# sensor_board.net
KiCad netlist of a schematic drawn in EAGLE
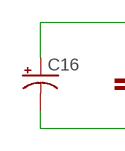
[diagram p0: schematic, sheet 1, part 1 of 2]
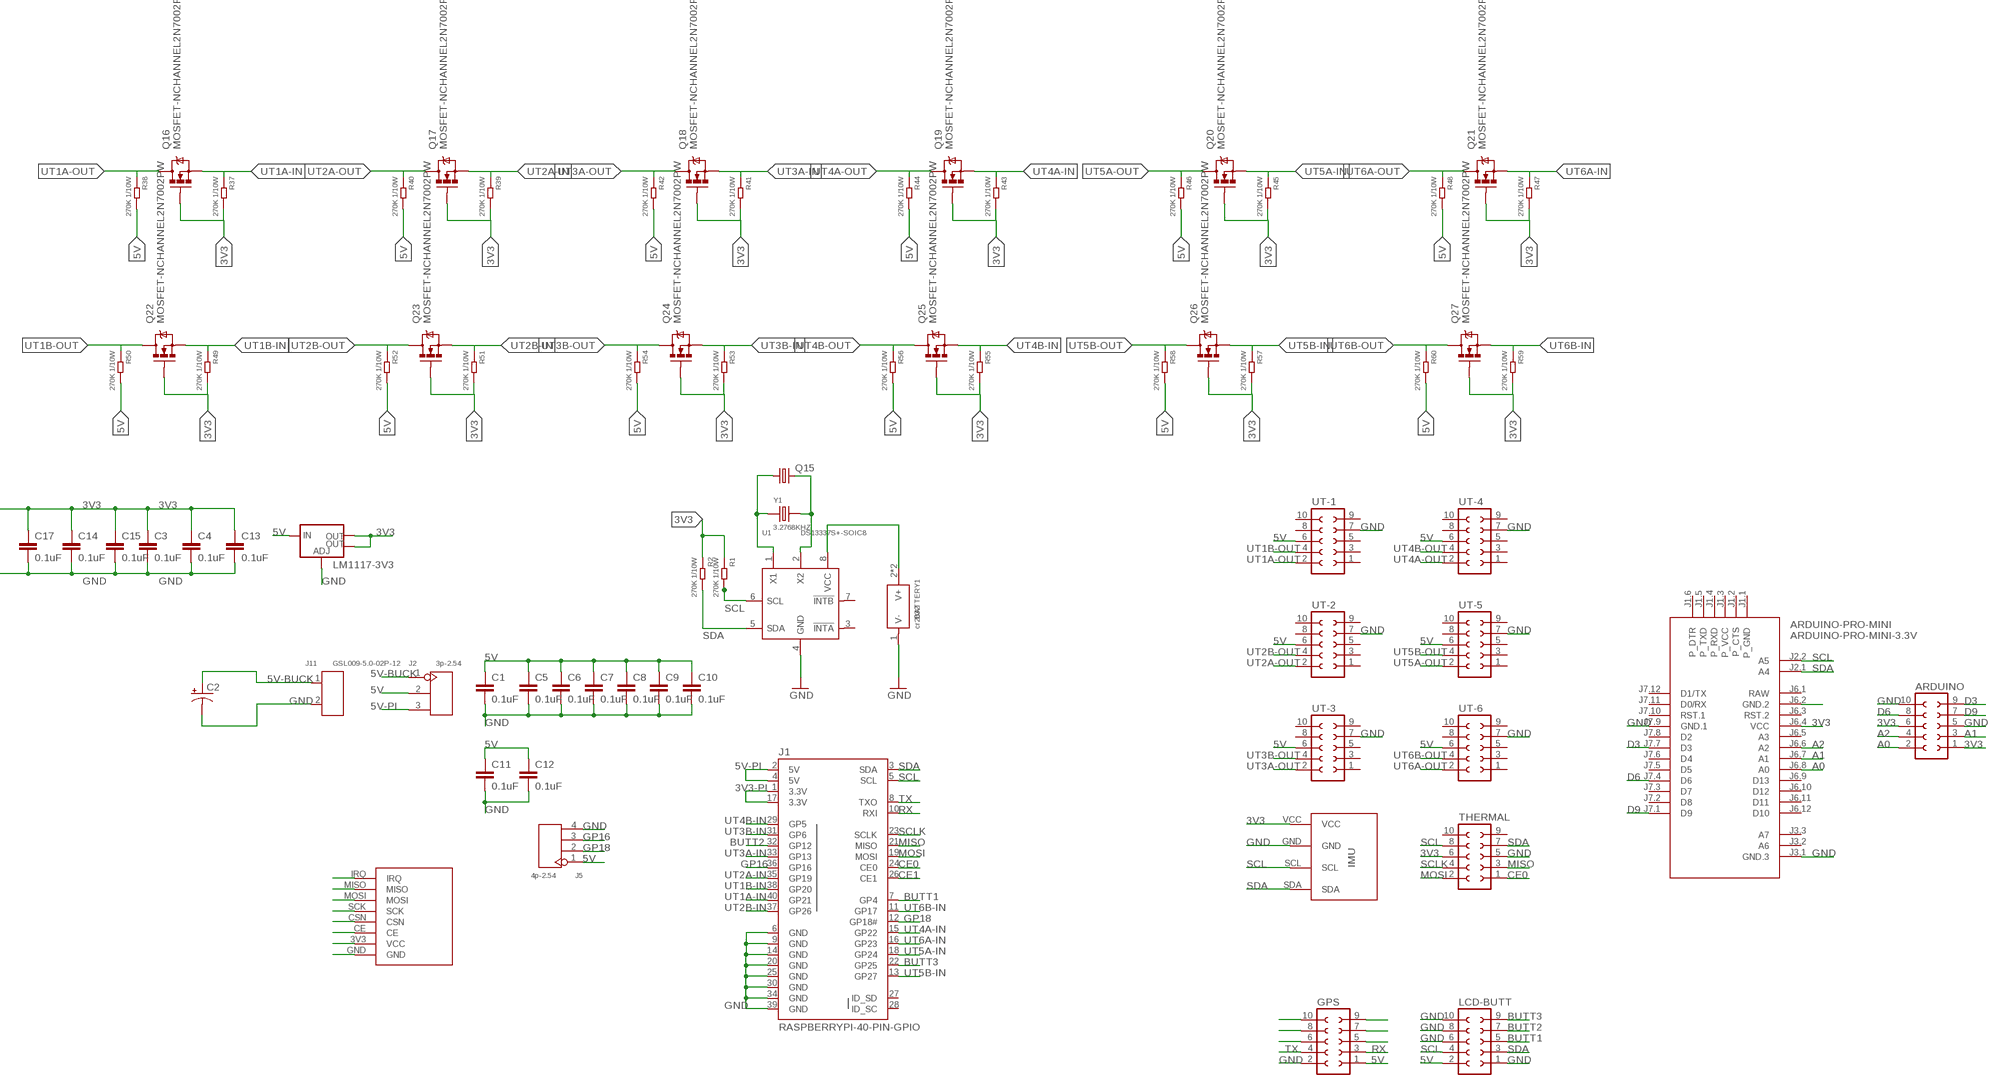
[diagram p1: schematic, sheet 1, part 2 of 2]

(export (version "E")
  (design (tool "Eeschema 10.0.6"))
  (components
    (comp (ref "ARDUINO")
      (value "SOCKET-10V")
      (footprint "eagle-import:S10V")
      (libsource (lib "eagle-import") (part "SOCKET-10V"))
    )
    (comp (ref "ARDUINO-PRO-MINI")
      (value "ARDUINO-PRO-MINI-3.3V")
      (footprint "eagle-import:ARDUINO-PRO-MINI")
      (libsource (lib "eagle-import") (part "ARDUINO-PRO-MINI-3.3V"))
    )
    (comp (ref "BATTERY1")
      (value "cr2032")
      (footprint "eagle-import:BAT2P-20.32-CR2032")
      (libsource (lib "eagle-import") (part "DIP-BATTERY-CELL-HOLDER(2032)"))
    )
    (comp (ref "C1")
      (value "0.1uF")
      (footprint "eagle-import:0603-CAP")
      (libsource (lib "eagle-import") (part "0.1UF-100V-10%(0603)"))
    )
    (comp (ref "C2")
      (value "100UF-25V-20%(PTH)")
      (footprint "eagle-import:CPOL-RADIAL-100UF-25V")
      (libsource (lib "eagle-import") (part "100UF-25V-20%(PTH)"))
    )
    (comp (ref "C3")
      (value "0.1uF")
      (footprint "eagle-import:0603-CAP")
      (libsource (lib "eagle-import") (part "0.1UF-100V-10%(0603)"))
    )
    (comp (ref "C4")
      (value "0.1uF")
      (footprint "eagle-import:0603-CAP")
      (libsource (lib "eagle-import") (part "0.1UF-100V-10%(0603)"))
    )
    (comp (ref "C5")
      (value "0.1uF")
      (footprint "eagle-import:0603-CAP")
      (libsource (lib "eagle-import") (part "0.1UF-100V-10%(0603)"))
    )
    (comp (ref "C6")
      (value "0.1uF")
      (footprint "eagle-import:0603-CAP")
      (libsource (lib "eagle-import") (part "0.1UF-100V-10%(0603)"))
    )
    (comp (ref "C7")
      (value "0.1uF")
      (footprint "eagle-import:0603-CAP")
      (libsource (lib "eagle-import") (part "0.1UF-100V-10%(0603)"))
    )
    (comp (ref "C8")
      (value "0.1uF")
      (footprint "eagle-import:0603-CAP")
      (libsource (lib "eagle-import") (part "0.1UF-100V-10%(0603)"))
    )
    (comp (ref "C9")
      (value "0.1uF")
      (footprint "eagle-import:0603-CAP")
      (libsource (lib "eagle-import") (part "0.1UF-100V-10%(0603)"))
    )
    (comp (ref "C10")
      (value "0.1uF")
      (footprint "eagle-import:0603-CAP")
      (libsource (lib "eagle-import") (part "0.1UF-100V-10%(0603)"))
    )
    (comp (ref "C11")
      (value "0.1uF")
      (footprint "eagle-import:0603-CAP")
      (libsource (lib "eagle-import") (part "0.1UF-100V-10%(0603)"))
    )
    (comp (ref "C12")
      (value "0.1uF")
      (footprint "eagle-import:0603-CAP")
      (libsource (lib "eagle-import") (part "0.1UF-100V-10%(0603)"))
    )
    (comp (ref "C13")
      (value "0.1uF")
      (footprint "eagle-import:0603-CAP")
      (libsource (lib "eagle-import") (part "0.1UF-100V-10%(0603)"))
    )
    (comp (ref "C14")
      (value "0.1uF")
      (footprint "eagle-import:0603-CAP")
      (libsource (lib "eagle-import") (part "0.1UF-100V-10%(0603)"))
    )
    (comp (ref "C15")
      (value "0.1uF")
      (footprint "eagle-import:0603-CAP")
      (libsource (lib "eagle-import") (part "0.1UF-100V-10%(0603)"))
    )
    (comp (ref "C16")
      (value "100UF-25V-20%(PTH)")
      (footprint "eagle-import:CPOL-RADIAL-100UF-25V")
      (libsource (lib "eagle-import") (part "100UF-25V-20%(PTH)"))
    )
    (comp (ref "C17")
      (value "0.1uF")
      (footprint "eagle-import:0603-CAP")
      (libsource (lib "eagle-import") (part "0.1UF-100V-10%(0603)"))
    )
    (comp (ref "GPS")
      (value "SOCKET-10V")
      (footprint "eagle-import:S10V")
      (libsource (lib "eagle-import") (part "SOCKET-10V"))
    )
    (comp (ref "J1")
      (value "RASPBERRYPI-40-PIN-GPIO")
      (footprint "eagle-import:2X20-SHROUDED")
      (libsource (lib "eagle-import") (part "RASPBERRYPI-40-PIN-GPIO"))
    )
    (comp (ref "J2")
      (value "3p-2.54")
      (footprint "eagle-import:H3-2.54")
      (fields (field (name "MPN") "F185-1103A0BSYA1"))
      (libsource (lib "eagle-import") (part "DIP-BLACK-FEMALE-HEADER-VERT(3P-2.54)"))
    )
    (comp (ref "J5")
      (value "4p-2.54")
      (footprint "eagle-import:H4-2.54")
      (fields (field (name "MPN") "F185-1104A1BSYA1"))
      (libsource (lib "eagle-import") (part "DIP-BLACK-FEMALE-HEADER-VERT(4P-2.54)"))
    )
    (comp (ref "J11")
      (value "GSL009-5.0-02P-12")
      (footprint "eagle-import:H2-5.0-10.5X8.0MM")
      (libsource (lib "eagle-import") (part "SCREW-TERMINAL-BLUE(2P-5.0)"))
    )
    (comp (ref "LCD-BUTT")
      (value "SOCKET-10V")
      (footprint "eagle-import:S10V")
      (libsource (lib "eagle-import") (part "SOCKET-10V"))
    )
    (comp (ref "LM1117-3V3")
      (value "V_REG_LM1117SOT223")
      (footprint "eagle-import:SOT223")
      (libsource (lib "eagle-import") (part "V_REG_LM1117SOT223"))
    )
    (comp (ref "Q15")
      (value "CRYSTALTC26H")
      (footprint "eagle-import:TC26H")
      (libsource (lib "eagle-import") (part "CRYSTALTC26H"))
    )
    (comp (ref "Q16")
      (value "MOSFET-NCHANNEL2N7002PW")
      (footprint "eagle-import:SOT323")
      (libsource (lib "eagle-import") (part "MOSFET-NCHANNEL2N7002PW"))
    )
    (comp (ref "Q17")
      (value "MOSFET-NCHANNEL2N7002PW")
      (footprint "eagle-import:SOT323")
      (libsource (lib "eagle-import") (part "MOSFET-NCHANNEL2N7002PW"))
    )
    (comp (ref "Q18")
      (value "MOSFET-NCHANNEL2N7002PW")
      (footprint "eagle-import:SOT323")
      (libsource (lib "eagle-import") (part "MOSFET-NCHANNEL2N7002PW"))
    )
    (comp (ref "Q19")
      (value "MOSFET-NCHANNEL2N7002PW")
      (footprint "eagle-import:SOT323")
      (libsource (lib "eagle-import") (part "MOSFET-NCHANNEL2N7002PW"))
    )
    (comp (ref "Q20")
      (value "MOSFET-NCHANNEL2N7002PW")
      (footprint "eagle-import:SOT323")
      (libsource (lib "eagle-import") (part "MOSFET-NCHANNEL2N7002PW"))
    )
    (comp (ref "Q21")
      (value "MOSFET-NCHANNEL2N7002PW")
      (footprint "eagle-import:SOT323")
      (libsource (lib "eagle-import") (part "MOSFET-NCHANNEL2N7002PW"))
    )
    (comp (ref "Q22")
      (value "MOSFET-NCHANNEL2N7002PW")
      (footprint "eagle-import:SOT323")
      (libsource (lib "eagle-import") (part "MOSFET-NCHANNEL2N7002PW"))
    )
    (comp (ref "Q23")
      (value "MOSFET-NCHANNEL2N7002PW")
      (footprint "eagle-import:SOT323")
      (libsource (lib "eagle-import") (part "MOSFET-NCHANNEL2N7002PW"))
    )
    (comp (ref "Q24")
      (value "MOSFET-NCHANNEL2N7002PW")
      (footprint "eagle-import:SOT323")
      (libsource (lib "eagle-import") (part "MOSFET-NCHANNEL2N7002PW"))
    )
    (comp (ref "Q25")
      (value "MOSFET-NCHANNEL2N7002PW")
      (footprint "eagle-import:SOT323")
      (libsource (lib "eagle-import") (part "MOSFET-NCHANNEL2N7002PW"))
    )
    (comp (ref "Q26")
      (value "MOSFET-NCHANNEL2N7002PW")
      (footprint "eagle-import:SOT323")
      (libsource (lib "eagle-import") (part "MOSFET-NCHANNEL2N7002PW"))
    )
    (comp (ref "Q27")
      (value "MOSFET-NCHANNEL2N7002PW")
      (footprint "eagle-import:SOT323")
      (libsource (lib "eagle-import") (part "MOSFET-NCHANNEL2N7002PW"))
    )
    (comp (ref "R1")
      (value "270K 1/10W")
      (footprint "eagle-import:R0603")
      (fields (field (name "MPN") "RC0603FR-07270KL"))
      (libsource (lib "eagle-import") (part "RC0603FR-0720RL(0603)"))
    )
    (comp (ref "R2")
      (value "270K 1/10W")
      (footprint "eagle-import:R0603")
      (fields (field (name "MPN") "RC0603FR-07270KL"))
      (libsource (lib "eagle-import") (part "RC0603FR-0720RL(0603)"))
    )
    (comp (ref "R37")
      (value "270K 1/10W")
      (footprint "eagle-import:R0603")
      (fields (field (name "MPN") "RC0603FR-07270KL"))
      (libsource (lib "eagle-import") (part "RC0603FR-0720RL(0603)"))
    )
    (comp (ref "R38")
      (value "270K 1/10W")
      (footprint "eagle-import:R0603")
      (fields (field (name "MPN") "RC0603FR-07270KL"))
      (libsource (lib "eagle-import") (part "RC0603FR-0720RL(0603)"))
    )
    (comp (ref "R39")
      (value "270K 1/10W")
      (footprint "eagle-import:R0603")
      (fields (field (name "MPN") "RC0603FR-07270KL"))
      (libsource (lib "eagle-import") (part "RC0603FR-0720RL(0603)"))
    )
    (comp (ref "R40")
      (value "270K 1/10W")
      (footprint "eagle-import:R0603")
      (fields (field (name "MPN") "RC0603FR-07270KL"))
      (libsource (lib "eagle-import") (part "RC0603FR-0720RL(0603)"))
    )
    (comp (ref "R41")
      (value "270K 1/10W")
      (footprint "eagle-import:R0603")
      (fields (field (name "MPN") "RC0603FR-07270KL"))
      (libsource (lib "eagle-import") (part "RC0603FR-0720RL(0603)"))
    )
    (comp (ref "R42")
      (value "270K 1/10W")
      (footprint "eagle-import:R0603")
      (fields (field (name "MPN") "RC0603FR-07270KL"))
      (libsource (lib "eagle-import") (part "RC0603FR-0720RL(0603)"))
    )
    (comp (ref "R43")
      (value "270K 1/10W")
      (footprint "eagle-import:R0603")
      (fields (field (name "MPN") "RC0603FR-07270KL"))
      (libsource (lib "eagle-import") (part "RC0603FR-0720RL(0603)"))
    )
    (comp (ref "R44")
      (value "270K 1/10W")
      (footprint "eagle-import:R0603")
      (fields (field (name "MPN") "RC0603FR-07270KL"))
      (libsource (lib "eagle-import") (part "RC0603FR-0720RL(0603)"))
    )
    (comp (ref "R45")
      (value "270K 1/10W")
      (footprint "eagle-import:R0603")
      (fields (field (name "MPN") "RC0603FR-07270KL"))
      (libsource (lib "eagle-import") (part "RC0603FR-0720RL(0603)"))
    )
    (comp (ref "R46")
      (value "270K 1/10W")
      (footprint "eagle-import:R0603")
      (fields (field (name "MPN") "RC0603FR-07270KL"))
      (libsource (lib "eagle-import") (part "RC0603FR-0720RL(0603)"))
    )
    (comp (ref "R47")
      (value "270K 1/10W")
      (footprint "eagle-import:R0603")
      (fields (field (name "MPN") "RC0603FR-07270KL"))
      (libsource (lib "eagle-import") (part "RC0603FR-0720RL(0603)"))
    )
    (comp (ref "R48")
      (value "270K 1/10W")
      (footprint "eagle-import:R0603")
      (fields (field (name "MPN") "RC0603FR-07270KL"))
      (libsource (lib "eagle-import") (part "RC0603FR-0720RL(0603)"))
    )
    (comp (ref "R49")
      (value "270K 1/10W")
      (footprint "eagle-import:R0603")
      (fields (field (name "MPN") "RC0603FR-07270KL"))
      (libsource (lib "eagle-import") (part "RC0603FR-0720RL(0603)"))
    )
    (comp (ref "R50")
      (value "270K 1/10W")
      (footprint "eagle-import:R0603")
      (fields (field (name "MPN") "RC0603FR-07270KL"))
      (libsource (lib "eagle-import") (part "RC0603FR-0720RL(0603)"))
    )
    (comp (ref "R51")
      (value "270K 1/10W")
      (footprint "eagle-import:R0603")
      (fields (field (name "MPN") "RC0603FR-07270KL"))
      (libsource (lib "eagle-import") (part "RC0603FR-0720RL(0603)"))
    )
    (comp (ref "R52")
      (value "270K 1/10W")
      (footprint "eagle-import:R0603")
      (fields (field (name "MPN") "RC0603FR-07270KL"))
      (libsource (lib "eagle-import") (part "RC0603FR-0720RL(0603)"))
    )
    (comp (ref "R53")
      (value "270K 1/10W")
      (footprint "eagle-import:R0603")
      (fields (field (name "MPN") "RC0603FR-07270KL"))
      (libsource (lib "eagle-import") (part "RC0603FR-0720RL(0603)"))
    )
    (comp (ref "R54")
      (value "270K 1/10W")
      (footprint "eagle-import:R0603")
      (fields (field (name "MPN") "RC0603FR-07270KL"))
      (libsource (lib "eagle-import") (part "RC0603FR-0720RL(0603)"))
    )
    (comp (ref "R55")
      (value "270K 1/10W")
      (footprint "eagle-import:R0603")
      (fields (field (name "MPN") "RC0603FR-07270KL"))
      (libsource (lib "eagle-import") (part "RC0603FR-0720RL(0603)"))
    )
    (comp (ref "R56")
      (value "270K 1/10W")
      (footprint "eagle-import:R0603")
      (fields (field (name "MPN") "RC0603FR-07270KL"))
      (libsource (lib "eagle-import") (part "RC0603FR-0720RL(0603)"))
    )
    (comp (ref "R57")
      (value "270K 1/10W")
      (footprint "eagle-import:R0603")
      (fields (field (name "MPN") "RC0603FR-07270KL"))
      (libsource (lib "eagle-import") (part "RC0603FR-0720RL(0603)"))
    )
    (comp (ref "R58")
      (value "270K 1/10W")
      (footprint "eagle-import:R0603")
      (fields (field (name "MPN") "RC0603FR-07270KL"))
      (libsource (lib "eagle-import") (part "RC0603FR-0720RL(0603)"))
    )
    (comp (ref "R59")
      (value "270K 1/10W")
      (footprint "eagle-import:R0603")
      (fields (field (name "MPN") "RC0603FR-07270KL"))
      (libsource (lib "eagle-import") (part "RC0603FR-0720RL(0603)"))
    )
    (comp (ref "R60")
      (value "270K 1/10W")
      (footprint "eagle-import:R0603")
      (fields (field (name "MPN") "RC0603FR-07270KL"))
      (libsource (lib "eagle-import") (part "RC0603FR-0720RL(0603)"))
    )
    (comp (ref "THERMAL")
      (value "SOCKET-10V")
      (footprint "eagle-import:S10V")
      (libsource (lib "eagle-import") (part "SOCKET-10V"))
    )
    (comp (ref "U$1")
      (value "IMU")
      (footprint "eagle-import:IMU")
      (libsource (lib "eagle-import") (part "IMU"))
    )
    (comp (ref "U$2")
      (value "NRF24L01+")
      (footprint "eagle-import:NRF24L01+")
      (libsource (lib "eagle-import") (part "NRF24L01+"))
    )
    (comp (ref "U1")
      (value "DS13337S+-SOIC8")
      (footprint "eagle-import:SOIC8-1.27-5X4MM")
      (fields (field (name "MPN") "DS1337S+"))
      (libsource (lib "eagle-import") (part "CLOCK-DS1337S+(SOIC8)"))
    )
    (comp (ref "UT-1")
      (value "SOCKET-10V")
      (footprint "eagle-import:S10V")
      (libsource (lib "eagle-import") (part "SOCKET-10V"))
    )
    (comp (ref "UT-2")
      (value "SOCKET-10V")
      (footprint "eagle-import:S10V")
      (libsource (lib "eagle-import") (part "SOCKET-10V"))
    )
    (comp (ref "UT-3")
      (value "SOCKET-10V")
      (footprint "eagle-import:S10V")
      (libsource (lib "eagle-import") (part "SOCKET-10V"))
    )
    (comp (ref "UT-4")
      (value "SOCKET-10V")
      (footprint "eagle-import:S10V")
      (libsource (lib "eagle-import") (part "SOCKET-10V"))
    )
    (comp (ref "UT-5")
      (value "SOCKET-10V")
      (footprint "eagle-import:S10V")
      (libsource (lib "eagle-import") (part "SOCKET-10V"))
    )
    (comp (ref "UT-6")
      (value "SOCKET-10V")
      (footprint "eagle-import:S10V")
      (libsource (lib "eagle-import") (part "SOCKET-10V"))
    )
    (comp (ref "Y1")
      (value "3.2768KHZ")
      (footprint "eagle-import:X2-SMD-L2.0X1.2X0.55MM")
      (fields (field (name "MPN") "FC-12M"))
      (libsource (lib "eagle-import") (part "SMD-CRYSTAL-32.768KHZ-12.5PF-20PPM-90K(2P-L2.0X1.2MM)"))
    )
  )
  (nets
    (net (code "1") (name "/3V3-PI") (class "Default")
      (node (ref "J1") (pin "1") (pinfunction "3.3V_1") (pintype "power_in"))
      (node (ref "J1") (pin "17") (pinfunction "3.3V_17") (pintype "power_in"))
    )
    (net (code "2") (name "/5V-BUCK") (class "Default")
      (node (ref "C2") (pin "1") (pinfunction "+_1") (pintype "passive"))
      (node (ref "J11") (pin "1") (pinfunction "1_1") (pintype "bidirectional"))
      (node (ref "J2") (pin "1") (pinfunction "P$1_1") (pintype "bidirectional"))
    )
    (net (code "3") (name "/5V-PI") (class "Default")
      (node (ref "J1") (pin "2") (pinfunction "5V_2") (pintype "power_in"))
      (node (ref "J1") (pin "4") (pinfunction "5V_4") (pintype "power_in"))
      (node (ref "J2") (pin "3") (pinfunction "P$3_3") (pintype "bidirectional"))
    )
    (net (code "4") (name "/A0") (class "Default")
      (node (ref "ARDUINO") (pin "2") (pinfunction "2_2") (pintype "passive"))
      (node (ref "ARDUINO-PRO-MINI") (pin "J6.8") (pinfunction "A0_J6.8") (pintype "bidirectional"))
    )
    (net (code "5") (name "/A1") (class "Default")
      (node (ref "ARDUINO") (pin "3") (pinfunction "3_3") (pintype "passive"))
      (node (ref "ARDUINO-PRO-MINI") (pin "J6.7") (pinfunction "A1_J6.7") (pintype "bidirectional"))
    )
    (net (code "6") (name "/A2") (class "Default")
      (node (ref "ARDUINO") (pin "4") (pinfunction "4_4") (pintype "passive"))
      (node (ref "ARDUINO-PRO-MINI") (pin "J6.6") (pinfunction "A2_J6.6") (pintype "bidirectional"))
    )
    (net (code "7") (name "/BUTT1") (class "Default")
      (node (ref "J1") (pin "7") (pinfunction "GP4_7") (pintype "bidirectional"))
      (node (ref "LCD-BUTT") (pin "5") (pinfunction "5_5") (pintype "passive"))
    )
    (net (code "8") (name "/BUTT2") (class "Default")
      (node (ref "J1") (pin "32") (pinfunction "GP12_32") (pintype "bidirectional"))
      (node (ref "LCD-BUTT") (pin "7") (pinfunction "7_7") (pintype "passive"))
    )
    (net (code "9") (name "/BUTT3") (class "Default")
      (node (ref "J1") (pin "22") (pinfunction "GP25_22") (pintype "bidirectional"))
      (node (ref "LCD-BUTT") (pin "9") (pinfunction "9_9") (pintype "passive"))
      (node (ref "U$2") (pin "CE") (pinfunction "CE_CE") (pintype "bidirectional"))
    )
    (net (code "10") (name "/CE0") (class "Default")
      (node (ref "J1") (pin "24") (pinfunction "CE0_24") (pintype "output"))
      (node (ref "THERMAL") (pin "1") (pinfunction "1_1") (pintype "passive"))
    )
    (net (code "11") (name "/CE1") (class "Default")
      (node (ref "J1") (pin "26") (pinfunction "CE1_26") (pintype "output"))
      (node (ref "U$2") (pin "CSN") (pinfunction "CSN_CSN") (pintype "bidirectional"))
    )
    (net (code "12") (name "/D3") (class "Default")
      (node (ref "ARDUINO") (pin "9") (pinfunction "9_9") (pintype "passive"))
      (node (ref "ARDUINO-PRO-MINI") (pin "J7.7") (pinfunction "D3_J7.7") (pintype "bidirectional"))
    )
    (net (code "13") (name "/D6") (class "Default")
      (node (ref "ARDUINO") (pin "8") (pinfunction "8_8") (pintype "passive"))
      (node (ref "ARDUINO-PRO-MINI") (pin "J7.4") (pinfunction "D6_J7.4") (pintype "bidirectional"))
    )
    (net (code "14") (name "/D9") (class "Default")
      (node (ref "ARDUINO") (pin "7") (pinfunction "7_7") (pintype "passive"))
      (node (ref "ARDUINO-PRO-MINI") (pin "J7.1") (pinfunction "D9_J7.1") (pintype "bidirectional"))
    )
    (net (code "15") (name "/GP16") (class "Default")
      (node (ref "J1") (pin "36") (pinfunction "GP16_36") (pintype "bidirectional"))
      (node (ref "J5") (pin "3") (pinfunction "P$3_3") (pintype "bidirectional"))
    )
    (net (code "16") (name "/GP18") (class "Default")
      (node (ref "J1") (pin "12") (pinfunction "GP18#_12") (pintype "bidirectional"))
      (node (ref "J5") (pin "2") (pinfunction "P$2_2") (pintype "bidirectional"))
    )
    (net (code "17") (name "/MISO") (class "Default")
      (node (ref "J1") (pin "21") (pinfunction "MISO_21") (pintype "input"))
      (node (ref "THERMAL") (pin "3") (pinfunction "3_3") (pintype "passive"))
      (node (ref "U$2") (pin "MISO") (pinfunction "MISO_MISO") (pintype "bidirectional"))
    )
    (net (code "18") (name "/MOSI") (class "Default")
      (node (ref "J1") (pin "19") (pinfunction "MOSI_19") (pintype "output"))
      (node (ref "THERMAL") (pin "2") (pinfunction "2_2") (pintype "passive"))
      (node (ref "U$2") (pin "MOSI") (pinfunction "MOSI_MOSI") (pintype "bidirectional"))
    )
    (net (code "19") (name "/RAW") (class "Default")
      (node (ref "ARDUINO-PRO-MINI") (pin "J6.1") (pinfunction "RAW_J6.1") (pintype "power_in"))
    )
    (net (code "20") (name "/RX") (class "Default")
      (node (ref "GPS") (pin "3") (pinfunction "3_3") (pintype "passive"))
      (node (ref "J1") (pin "10") (pinfunction "RXI_10") (pintype "input"))
    )
    (net (code "21") (name "/SCL") (class "Default")
      (node (ref "ARDUINO-PRO-MINI") (pin "J2.2") (pinfunction "A5_J2.2") (pintype "bidirectional"))
      (node (ref "J1") (pin "5") (pinfunction "SCL_5") (pintype "bidirectional"))
      (node (ref "LCD-BUTT") (pin "4") (pinfunction "4_4") (pintype "passive"))
      (node (ref "R1") (pin "2") (pinfunction "2_2") (pintype "passive"))
      (node (ref "THERMAL") (pin "8") (pinfunction "8_8") (pintype "passive"))
      (node (ref "U$1") (pin "SCL") (pinfunction "SCL_SCL") (pintype "bidirectional"))
      (node (ref "U1") (pin "6") (pinfunction "SCL_6") (pintype "bidirectional"))
    )
    (net (code "22") (name "/SCLK") (class "Default")
      (node (ref "J1") (pin "23") (pinfunction "SCLK_23") (pintype "output"))
      (node (ref "THERMAL") (pin "4") (pinfunction "4_4") (pintype "passive"))
      (node (ref "U$2") (pin "SCK") (pinfunction "SCK_SCK") (pintype "bidirectional"))
    )
    (net (code "23") (name "/SDA") (class "Default")
      (node (ref "ARDUINO-PRO-MINI") (pin "J2.1") (pinfunction "A4_J2.1") (pintype "bidirectional"))
      (node (ref "J1") (pin "3") (pinfunction "SDA_3") (pintype "bidirectional"))
      (node (ref "LCD-BUTT") (pin "3") (pinfunction "3_3") (pintype "passive"))
      (node (ref "R2") (pin "2") (pinfunction "2_2") (pintype "passive"))
      (node (ref "THERMAL") (pin "7") (pinfunction "7_7") (pintype "passive"))
      (node (ref "U$1") (pin "SDA") (pinfunction "SDA_SDA") (pintype "bidirectional"))
      (node (ref "U1") (pin "5") (pinfunction "SDA_5") (pintype "bidirectional"))
    )
    (net (code "24") (name "/TX") (class "Default")
      (node (ref "GPS") (pin "4") (pinfunction "4_4") (pintype "passive"))
      (node (ref "J1") (pin "8") (pinfunction "TXO_8") (pintype "output"))
    )
    (net (code "25") (name "3V3") (class "Default")
      (node (ref "ARDUINO") (pin "1") (pinfunction "1_1") (pintype "passive"))
      (node (ref "ARDUINO") (pin "6") (pinfunction "6_6") (pintype "passive"))
      (node (ref "ARDUINO-PRO-MINI") (pin "J6.4") (pinfunction "VCC_J6.4") (pintype "power_in"))
      (node (ref "C13") (pin "1") (pinfunction "1_1") (pintype "passive"))
      (node (ref "C14") (pin "1") (pinfunction "1_1") (pintype "passive"))
      (node (ref "C15") (pin "1") (pinfunction "1_1") (pintype "passive"))
      (node (ref "C16") (pin "1") (pinfunction "+_1") (pintype "passive"))
      (node (ref "C17") (pin "1") (pinfunction "1_1") (pintype "passive"))
      (node (ref "C3") (pin "1") (pinfunction "1_1") (pintype "passive"))
      (node (ref "C4") (pin "1") (pinfunction "1_1") (pintype "passive"))
      (node (ref "LM1117-3V3") (pin "2") (pinfunction "OUT_2") (pintype "output"))
      (node (ref "LM1117-3V3") (pin "4") (pinfunction "OUT_4") (pintype "output"))
      (node (ref "Q16") (pin "1") (pinfunction "G_1") (pintype "passive"))
      (node (ref "Q17") (pin "1") (pinfunction "G_1") (pintype "passive"))
      (node (ref "Q18") (pin "1") (pinfunction "G_1") (pintype "passive"))
      (node (ref "Q19") (pin "1") (pinfunction "G_1") (pintype "passive"))
      (node (ref "Q20") (pin "1") (pinfunction "G_1") (pintype "passive"))
      (node (ref "Q21") (pin "1") (pinfunction "G_1") (pintype "passive"))
      (node (ref "Q22") (pin "1") (pinfunction "G_1") (pintype "passive"))
      (node (ref "Q23") (pin "1") (pinfunction "G_1") (pintype "passive"))
      (node (ref "Q24") (pin "1") (pinfunction "G_1") (pintype "passive"))
      (node (ref "Q25") (pin "1") (pinfunction "G_1") (pintype "passive"))
      (node (ref "Q26") (pin "1") (pinfunction "G_1") (pintype "passive"))
      (node (ref "Q27") (pin "1") (pinfunction "G_1") (pintype "passive"))
      (node (ref "R1") (pin "1") (pinfunction "1_1") (pintype "passive"))
      (node (ref "R2") (pin "1") (pinfunction "1_1") (pintype "passive"))
      (node (ref "R37") (pin "2") (pinfunction "2_2") (pintype "passive"))
      (node (ref "R39") (pin "2") (pinfunction "2_2") (pintype "passive"))
      (node (ref "R41") (pin "2") (pinfunction "2_2") (pintype "passive"))
      (node (ref "R43") (pin "2") (pinfunction "2_2") (pintype "passive"))
      (node (ref "R45") (pin "2") (pinfunction "2_2") (pintype "passive"))
      (node (ref "R47") (pin "2") (pinfunction "2_2") (pintype "passive"))
      (node (ref "R49") (pin "2") (pinfunction "2_2") (pintype "passive"))
      (node (ref "R51") (pin "2") (pinfunction "2_2") (pintype "passive"))
      (node (ref "R53") (pin "2") (pinfunction "2_2") (pintype "passive"))
      (node (ref "R55") (pin "2") (pinfunction "2_2") (pintype "passive"))
      (node (ref "R57") (pin "2") (pinfunction "2_2") (pintype "passive"))
      (node (ref "R59") (pin "2") (pinfunction "2_2") (pintype "passive"))
      (node (ref "THERMAL") (pin "6") (pinfunction "6_6") (pintype "passive"))
      (node (ref "U$1") (pin "VCC") (pinfunction "VCC_VCC") (pintype "bidirectional"))
      (node (ref "U$2") (pin "3V3") (pinfunction "VCC_3V3") (pintype "bidirectional"))
    )
    (net (code "26") (name "5V") (class "Default")
      (node (ref "C1") (pin "1") (pinfunction "1_1") (pintype "passive"))
      (node (ref "C10") (pin "1") (pinfunction "1_1") (pintype "passive"))
      (node (ref "C11") (pin "1") (pinfunction "1_1") (pintype "passive"))
      (node (ref "C12") (pin "1") (pinfunction "1_1") (pintype "passive"))
      (node (ref "C5") (pin "1") (pinfunction "1_1") (pintype "passive"))
      (node (ref "C6") (pin "1") (pinfunction "1_1") (pintype "passive"))
      (node (ref "C7") (pin "1") (pinfunction "1_1") (pintype "passive"))
      (node (ref "C8") (pin "1") (pinfunction "1_1") (pintype "passive"))
      (node (ref "C9") (pin "1") (pinfunction "1_1") (pintype "passive"))
      (node (ref "GPS") (pin "1") (pinfunction "1_1") (pintype "passive"))
      (node (ref "J2") (pin "2") (pinfunction "P$2_2") (pintype "bidirectional"))
      (node (ref "J5") (pin "1") (pinfunction "P$1_1") (pintype "bidirectional"))
      (node (ref "LCD-BUTT") (pin "2") (pinfunction "2_2") (pintype "passive"))
      (node (ref "LM1117-3V3") (pin "3") (pinfunction "IN_3") (pintype "input"))
      (node (ref "R38") (pin "2") (pinfunction "2_2") (pintype "passive"))
      (node (ref "R40") (pin "2") (pinfunction "2_2") (pintype "passive"))
      (node (ref "R42") (pin "2") (pinfunction "2_2") (pintype "passive"))
      (node (ref "R44") (pin "2") (pinfunction "2_2") (pintype "passive"))
      (node (ref "R46") (pin "2") (pinfunction "2_2") (pintype "passive"))
      (node (ref "R48") (pin "2") (pinfunction "2_2") (pintype "passive"))
      (node (ref "R50") (pin "2") (pinfunction "2_2") (pintype "passive"))
      (node (ref "R52") (pin "2") (pinfunction "2_2") (pintype "passive"))
      (node (ref "R54") (pin "2") (pinfunction "2_2") (pintype "passive"))
      (node (ref "R56") (pin "2") (pinfunction "2_2") (pintype "passive"))
      (node (ref "R58") (pin "2") (pinfunction "2_2") (pintype "passive"))
      (node (ref "R60") (pin "2") (pinfunction "2_2") (pintype "passive"))
      (node (ref "UT-1") (pin "6") (pinfunction "6_6") (pintype "passive"))
      (node (ref "UT-2") (pin "6") (pinfunction "6_6") (pintype "passive"))
      (node (ref "UT-3") (pin "6") (pinfunction "6_6") (pintype "passive"))
      (node (ref "UT-4") (pin "6") (pinfunction "6_6") (pintype "passive"))
      (node (ref "UT-5") (pin "6") (pinfunction "6_6") (pintype "passive"))
      (node (ref "UT-6") (pin "6") (pinfunction "6_6") (pintype "passive"))
    )
    (net (code "27") (name "GND") (class "Default")
      (node (ref "ARDUINO") (pin "10") (pinfunction "10_10") (pintype "passive"))
      (node (ref "ARDUINO") (pin "5") (pinfunction "5_5") (pintype "passive"))
      (node (ref "ARDUINO-PRO-MINI") (pin "J3.1") (pinfunction "GND.3_J3.1") (pintype "bidirectional"))
      (node (ref "ARDUINO-PRO-MINI") (pin "J6.2") (pinfunction "GND.2_J6.2") (pintype "power_in"))
      (node (ref "ARDUINO-PRO-MINI") (pin "J7.9") (pinfunction "GND.1_J7.9") (pintype "power_in"))
      (node (ref "BATTERY1") (pin "1") (pinfunction "V-_1") (pintype "bidirectional"))
      (node (ref "C1") (pin "2") (pinfunction "2_2") (pintype "passive"))
      (node (ref "C10") (pin "2") (pinfunction "2_2") (pintype "passive"))
      (node (ref "C11") (pin "2") (pinfunction "2_2") (pintype "passive"))
      (node (ref "C12") (pin "2") (pinfunction "2_2") (pintype "passive"))
      (node (ref "C13") (pin "2") (pinfunction "2_2") (pintype "passive"))
      (node (ref "C14") (pin "2") (pinfunction "2_2") (pintype "passive"))
      (node (ref "C15") (pin "2") (pinfunction "2_2") (pintype "passive"))
      (node (ref "C16") (pin "2") (pinfunction "-_2") (pintype "passive"))
      (node (ref "C17") (pin "2") (pinfunction "2_2") (pintype "passive"))
      (node (ref "C2") (pin "2") (pinfunction "-_2") (pintype "passive"))
      (node (ref "C3") (pin "2") (pinfunction "2_2") (pintype "passive"))
      (node (ref "C4") (pin "2") (pinfunction "2_2") (pintype "passive"))
      (node (ref "C5") (pin "2") (pinfunction "2_2") (pintype "passive"))
      (node (ref "C6") (pin "2") (pinfunction "2_2") (pintype "passive"))
      (node (ref "C7") (pin "2") (pinfunction "2_2") (pintype "passive"))
      (node (ref "C8") (pin "2") (pinfunction "2_2") (pintype "passive"))
      (node (ref "C9") (pin "2") (pinfunction "2_2") (pintype "passive"))
      (node (ref "GPS") (pin "2") (pinfunction "2_2") (pintype "passive"))
      (node (ref "J1") (pin "14") (pinfunction "GND_14") (pintype "power_in"))
      (node (ref "J1") (pin "20") (pinfunction "GND_20") (pintype "power_in"))
      (node (ref "J1") (pin "25") (pinfunction "GND_25") (pintype "power_in"))
      (node (ref "J1") (pin "30") (pinfunction "GND_30") (pintype "power_in"))
      (node (ref "J1") (pin "34") (pinfunction "GND_34") (pintype "power_in"))
      (node (ref "J1") (pin "39") (pinfunction "GND_39") (pintype "power_in"))
      (node (ref "J1") (pin "6") (pinfunction "GND_6") (pintype "power_in"))
      (node (ref "J1") (pin "9") (pinfunction "GND_9") (pintype "power_in"))
      (node (ref "J11") (pin "2") (pinfunction "2_2") (pintype "bidirectional"))
      (node (ref "J5") (pin "4") (pinfunction "P$4_4") (pintype "bidirectional"))
      (node (ref "LCD-BUTT") (pin "1") (pinfunction "1_1") (pintype "passive"))
      (node (ref "LCD-BUTT") (pin "10") (pinfunction "10_10") (pintype "passive"))
      (node (ref "LCD-BUTT") (pin "6") (pinfunction "6_6") (pintype "passive"))
      (node (ref "LCD-BUTT") (pin "8") (pinfunction "8_8") (pintype "passive"))
      (node (ref "LM1117-3V3") (pin "1") (pinfunction "ADJ_1") (pintype "input"))
      (node (ref "THERMAL") (pin "5") (pinfunction "5_5") (pintype "passive"))
      (node (ref "U$1") (pin "GND") (pinfunction "GND_GND") (pintype "bidirectional"))
      (node (ref "U$2") (pin "GND") (pinfunction "GND_GND") (pintype "bidirectional"))
      (node (ref "U1") (pin "4") (pinfunction "GND_4") (pintype "bidirectional"))
      (node (ref "UT-1") (pin "7") (pinfunction "7_7") (pintype "passive"))
      (node (ref "UT-2") (pin "7") (pinfunction "7_7") (pintype "passive"))
      (node (ref "UT-3") (pin "7") (pinfunction "7_7") (pintype "passive"))
      (node (ref "UT-4") (pin "7") (pinfunction "7_7") (pintype "passive"))
      (node (ref "UT-5") (pin "7") (pinfunction "7_7") (pintype "passive"))
      (node (ref "UT-6") (pin "7") (pinfunction "7_7") (pintype "passive"))
    )
    (net (code "28") (name "Net-(U1-VCC)") (class "Default")
      (node (ref "BATTERY1") (pin "2") (pinfunction "V+_2") (pintype "bidirectional"))
      (node (ref "BATTERY1") (pin "3") (pinfunction "V+_3") (pintype "bidirectional"))
      (node (ref "U1") (pin "8") (pinfunction "VCC_8") (pintype "bidirectional"))
    )
    (net (code "29") (name "Net-(U1-X1)") (class "Default")
      (node (ref "Q15") (pin "1") (pinfunction "1_1") (pintype "passive"))
      (node (ref "U1") (pin "1") (pinfunction "X1_1") (pintype "bidirectional"))
      (node (ref "Y1") (pin "1") (pinfunction "1_1") (pintype "passive"))
    )
    (net (code "30") (name "Net-(U1-X2)") (class "Default")
      (node (ref "Q15") (pin "2") (pinfunction "2_2") (pintype "passive"))
      (node (ref "U1") (pin "2") (pinfunction "X2_2") (pintype "bidirectional"))
      (node (ref "Y1") (pin "2") (pinfunction "2_2") (pintype "passive"))
    )
    (net (code "31") (name "UT1A-IN") (class "Default")
      (node (ref "J1") (pin "40") (pinfunction "GP21_40") (pintype "bidirectional"))
      (node (ref "Q16") (pin "2") (pinfunction "S_2") (pintype "passive"))
      (node (ref "R37") (pin "1") (pinfunction "1_1") (pintype "passive"))
    )
    (net (code "32") (name "UT1A-OUT") (class "Default")
      (node (ref "Q16") (pin "3") (pinfunction "D_3") (pintype "passive"))
      (node (ref "R38") (pin "1") (pinfunction "1_1") (pintype "passive"))
      (node (ref "UT-1") (pin "2") (pinfunction "2_2") (pintype "passive"))
    )
    (net (code "33") (name "UT1B-IN") (class "Default")
      (node (ref "J1") (pin "38") (pinfunction "GP20_38") (pintype "bidirectional"))
      (node (ref "Q22") (pin "2") (pinfunction "S_2") (pintype "passive"))
      (node (ref "R49") (pin "1") (pinfunction "1_1") (pintype "passive"))
    )
    (net (code "34") (name "UT1B-OUT") (class "Default")
      (node (ref "Q22") (pin "3") (pinfunction "D_3") (pintype "passive"))
      (node (ref "R50") (pin "1") (pinfunction "1_1") (pintype "passive"))
      (node (ref "UT-1") (pin "4") (pinfunction "4_4") (pintype "passive"))
    )
    (net (code "35") (name "UT2A-IN") (class "Default")
      (node (ref "J1") (pin "35") (pinfunction "GP19_35") (pintype "bidirectional"))
      (node (ref "Q17") (pin "2") (pinfunction "S_2") (pintype "passive"))
      (node (ref "R39") (pin "1") (pinfunction "1_1") (pintype "passive"))
    )
    (net (code "36") (name "UT2A-OUT") (class "Default")
      (node (ref "Q17") (pin "3") (pinfunction "D_3") (pintype "passive"))
      (node (ref "R40") (pin "1") (pinfunction "1_1") (pintype "passive"))
      (node (ref "UT-2") (pin "2") (pinfunction "2_2") (pintype "passive"))
    )
    (net (code "37") (name "UT2B-IN") (class "Default")
      (node (ref "J1") (pin "37") (pinfunction "GP26_37") (pintype "bidirectional"))
      (node (ref "Q23") (pin "2") (pinfunction "S_2") (pintype "passive"))
      (node (ref "R51") (pin "1") (pinfunction "1_1") (pintype "passive"))
    )
    (net (code "38") (name "UT2B-OUT") (class "Default")
      (node (ref "Q23") (pin "3") (pinfunction "D_3") (pintype "passive"))
      (node (ref "R52") (pin "1") (pinfunction "1_1") (pintype "passive"))
      (node (ref "UT-2") (pin "4") (pinfunction "4_4") (pintype "passive"))
    )
    (net (code "39") (name "UT3A-IN") (class "Default")
      (node (ref "J1") (pin "33") (pinfunction "GP13_33") (pintype "bidirectional"))
      (node (ref "Q18") (pin "2") (pinfunction "S_2") (pintype "passive"))
      (node (ref "R41") (pin "1") (pinfunction "1_1") (pintype "passive"))
    )
    (net (code "40") (name "UT3A-OUT") (class "Default")
      (node (ref "Q18") (pin "3") (pinfunction "D_3") (pintype "passive"))
      (node (ref "R42") (pin "1") (pinfunction "1_1") (pintype "passive"))
      (node (ref "UT-3") (pin "2") (pinfunction "2_2") (pintype "passive"))
    )
    (net (code "41") (name "UT3B-IN") (class "Default")
      (node (ref "J1") (pin "31") (pinfunction "GP6_31") (pintype "bidirectional"))
      (node (ref "Q24") (pin "2") (pinfunction "S_2") (pintype "passive"))
      (node (ref "R53") (pin "1") (pinfunction "1_1") (pintype "passive"))
    )
    (net (code "42") (name "UT3B-OUT") (class "Default")
      (node (ref "Q24") (pin "3") (pinfunction "D_3") (pintype "passive"))
      (node (ref "R54") (pin "1") (pinfunction "1_1") (pintype "passive"))
      (node (ref "UT-3") (pin "4") (pinfunction "4_4") (pintype "passive"))
    )
    (net (code "43") (name "UT4A-IN") (class "Default")
      (node (ref "J1") (pin "15") (pinfunction "GP22_15") (pintype "bidirectional"))
      (node (ref "Q19") (pin "2") (pinfunction "S_2") (pintype "passive"))
      (node (ref "R43") (pin "1") (pinfunction "1_1") (pintype "passive"))
    )
    (net (code "44") (name "UT4A-OUT") (class "Default")
      (node (ref "Q19") (pin "3") (pinfunction "D_3") (pintype "passive"))
      (node (ref "R44") (pin "1") (pinfunction "1_1") (pintype "passive"))
      (node (ref "UT-4") (pin "2") (pinfunction "2_2") (pintype "passive"))
    )
    (net (code "45") (name "UT4B-IN") (class "Default")
      (node (ref "J1") (pin "29") (pinfunction "GP5_29") (pintype "bidirectional"))
      (node (ref "Q25") (pin "2") (pinfunction "S_2") (pintype "passive"))
      (node (ref "R55") (pin "1") (pinfunction "1_1") (pintype "passive"))
    )
    (net (code "46") (name "UT4B-OUT") (class "Default")
      (node (ref "Q25") (pin "3") (pinfunction "D_3") (pintype "passive"))
      (node (ref "R56") (pin "1") (pinfunction "1_1") (pintype "passive"))
      (node (ref "UT-4") (pin "4") (pinfunction "4_4") (pintype "passive"))
    )
    (net (code "47") (name "UT5A-IN") (class "Default")
      (node (ref "J1") (pin "18") (pinfunction "GP24_18") (pintype "bidirectional"))
      (node (ref "Q20") (pin "2") (pinfunction "S_2") (pintype "passive"))
      (node (ref "R45") (pin "1") (pinfunction "1_1") (pintype "passive"))
    )
    (net (code "48") (name "UT5A-OUT") (class "Default")
      (node (ref "Q20") (pin "3") (pinfunction "D_3") (pintype "passive"))
      (node (ref "R46") (pin "1") (pinfunction "1_1") (pintype "passive"))
      (node (ref "UT-5") (pin "2") (pinfunction "2_2") (pintype "passive"))
    )
    (net (code "49") (name "UT5B-IN") (class "Default")
      (node (ref "J1") (pin "13") (pinfunction "GP27_13") (pintype "bidirectional"))
      (node (ref "Q26") (pin "2") (pinfunction "S_2") (pintype "passive"))
      (node (ref "R57") (pin "1") (pinfunction "1_1") (pintype "passive"))
    )
    (net (code "50") (name "UT5B-OUT") (class "Default")
      (node (ref "Q26") (pin "3") (pinfunction "D_3") (pintype "passive"))
      (node (ref "R58") (pin "1") (pinfunction "1_1") (pintype "passive"))
      (node (ref "UT-5") (pin "4") (pinfunction "4_4") (pintype "passive"))
    )
    (net (code "51") (name "UT6A-IN") (class "Default")
      (node (ref "J1") (pin "16") (pinfunction "GP23_16") (pintype "bidirectional"))
      (node (ref "Q21") (pin "2") (pinfunction "S_2") (pintype "passive"))
      (node (ref "R47") (pin "1") (pinfunction "1_1") (pintype "passive"))
    )
    (net (code "52") (name "UT6A-OUT") (class "Default")
      (node (ref "Q21") (pin "3") (pinfunction "D_3") (pintype "passive"))
      (node (ref "R48") (pin "1") (pinfunction "1_1") (pintype "passive"))
      (node (ref "UT-6") (pin "2") (pinfunction "2_2") (pintype "passive"))
    )
    (net (code "53") (name "UT6B-IN") (class "Default")
      (node (ref "J1") (pin "11") (pinfunction "GP17_11") (pintype "bidirectional"))
      (node (ref "Q27") (pin "2") (pinfunction "S_2") (pintype "passive"))
      (node (ref "R59") (pin "1") (pinfunction "1_1") (pintype "passive"))
    )
    (net (code "54") (name "UT6B-OUT") (class "Default")
      (node (ref "Q27") (pin "3") (pinfunction "D_3") (pintype "passive"))
      (node (ref "R60") (pin "1") (pinfunction "1_1") (pintype "passive"))
      (node (ref "UT-6") (pin "4") (pinfunction "4_4") (pintype "passive"))
    )
    (net (code "55") (name "unconnected-(ARDUINO-PRO-MINI-A3-PadJ6.5)") (class "Default")
      (node (ref "ARDUINO-PRO-MINI") (pin "J6.5") (pinfunction "A3_J6.5") (pintype "bidirectional"))
    )
    (net (code "56") (name "unconnected-(ARDUINO-PRO-MINI-A6-PadJ3.2)") (class "Default")
      (node (ref "ARDUINO-PRO-MINI") (pin "J3.2") (pinfunction "A6_J3.2") (pintype "bidirectional"))
    )
    (net (code "57") (name "unconnected-(ARDUINO-PRO-MINI-A7-PadJ3.3)") (class "Default")
      (node (ref "ARDUINO-PRO-MINI") (pin "J3.3") (pinfunction "A7_J3.3") (pintype "bidirectional"))
    )
    (net (code "58") (name "unconnected-(ARDUINO-PRO-MINI-D0{slash}RX-PadJ7.11)") (class "Default")
      (node (ref "ARDUINO-PRO-MINI") (pin "J7.11") (pinfunction "D0/RX_J7.11") (pintype "bidirectional"))
    )
    (net (code "59") (name "unconnected-(ARDUINO-PRO-MINI-D1{slash}TX-PadJ7.12)") (class "Default")
      (node (ref "ARDUINO-PRO-MINI") (pin "J7.12") (pinfunction "D1/TX_J7.12") (pintype "bidirectional"))
    )
    (net (code "60") (name "unconnected-(ARDUINO-PRO-MINI-D2-PadJ7.8)") (class "Default")
      (node (ref "ARDUINO-PRO-MINI") (pin "J7.8") (pinfunction "D2_J7.8") (pintype "bidirectional"))
    )
    (net (code "61") (name "unconnected-(ARDUINO-PRO-MINI-D4-PadJ7.6)") (class "Default")
      (node (ref "ARDUINO-PRO-MINI") (pin "J7.6") (pinfunction "D4_J7.6") (pintype "bidirectional"))
    )
    (net (code "62") (name "unconnected-(ARDUINO-PRO-MINI-D5-PadJ7.5)") (class "Default")
      (node (ref "ARDUINO-PRO-MINI") (pin "J7.5") (pinfunction "D5_J7.5") (pintype "bidirectional"))
    )
    (net (code "63") (name "unconnected-(ARDUINO-PRO-MINI-D7-PadJ7.3)") (class "Default")
      (node (ref "ARDUINO-PRO-MINI") (pin "J7.3") (pinfunction "D7_J7.3") (pintype "bidirectional"))
    )
    (net (code "64") (name "unconnected-(ARDUINO-PRO-MINI-D8-PadJ7.2)") (class "Default")
      (node (ref "ARDUINO-PRO-MINI") (pin "J7.2") (pinfunction "D8_J7.2") (pintype "bidirectional"))
    )
    (net (code "65") (name "unconnected-(ARDUINO-PRO-MINI-D10-PadJ6.12)") (class "Default")
      (node (ref "ARDUINO-PRO-MINI") (pin "J6.12") (pinfunction "D10_J6.12") (pintype "bidirectional"))
    )
    (net (code "66") (name "unconnected-(ARDUINO-PRO-MINI-D11-PadJ6.11)") (class "Default")
      (node (ref "ARDUINO-PRO-MINI") (pin "J6.11") (pinfunction "D11_J6.11") (pintype "bidirectional"))
    )
    (net (code "67") (name "unconnected-(ARDUINO-PRO-MINI-D12-PadJ6.10)") (class "Default")
      (node (ref "ARDUINO-PRO-MINI") (pin "J6.10") (pinfunction "D12_J6.10") (pintype "bidirectional"))
    )
    (net (code "68") (name "unconnected-(ARDUINO-PRO-MINI-D13-PadJ6.9)") (class "Default")
      (node (ref "ARDUINO-PRO-MINI") (pin "J6.9") (pinfunction "D13_J6.9") (pintype "bidirectional"))
    )
    (net (code "69") (name "unconnected-(ARDUINO-PRO-MINI-P_CTS-PadJ1.2)") (class "Default")
      (node (ref "ARDUINO-PRO-MINI") (pin "J1.2") (pinfunction "P_CTS_J1.2") (pintype "bidirectional"))
    )
    (net (code "70") (name "unconnected-(ARDUINO-PRO-MINI-P_DTR-PadJ1.6)") (class "Default")
      (node (ref "ARDUINO-PRO-MINI") (pin "J1.6") (pinfunction "P_DTR_J1.6") (pintype "bidirectional"))
    )
    (net (code "71") (name "unconnected-(ARDUINO-PRO-MINI-P_GND-PadJ1.1)") (class "Default")
      (node (ref "ARDUINO-PRO-MINI") (pin "J1.1") (pinfunction "P_GND_J1.1") (pintype "bidirectional"))
    )
    (net (code "72") (name "unconnected-(ARDUINO-PRO-MINI-P_RXD-PadJ1.4)") (class "Default")
      (node (ref "ARDUINO-PRO-MINI") (pin "J1.4") (pinfunction "P_RXD_J1.4") (pintype "bidirectional"))
    )
    (net (code "73") (name "unconnected-(ARDUINO-PRO-MINI-P_TXD-PadJ1.5)") (class "Default")
      (node (ref "ARDUINO-PRO-MINI") (pin "J1.5") (pinfunction "P_TXD_J1.5") (pintype "bidirectional"))
    )
    (net (code "74") (name "unconnected-(ARDUINO-PRO-MINI-P_VCC-PadJ1.3)") (class "Default")
      (node (ref "ARDUINO-PRO-MINI") (pin "J1.3") (pinfunction "P_VCC_J1.3") (pintype "bidirectional"))
    )
    (net (code "75") (name "unconnected-(ARDUINO-PRO-MINI-RST.1-PadJ7.10)") (class "Default")
      (node (ref "ARDUINO-PRO-MINI") (pin "J7.10") (pinfunction "RST.1_J7.10") (pintype "bidirectional"))
    )
    (net (code "76") (name "unconnected-(ARDUINO-PRO-MINI-RST.2-PadJ6.3)") (class "Default")
      (node (ref "ARDUINO-PRO-MINI") (pin "J6.3") (pinfunction "RST.2_J6.3") (pintype "bidirectional"))
    )
    (net (code "77") (name "unconnected-(GPS-Pad5)") (class "Default")
      (node (ref "GPS") (pin "5") (pinfunction "5_5") (pintype "passive"))
    )
    (net (code "78") (name "unconnected-(GPS-Pad6)") (class "Default")
      (node (ref "GPS") (pin "6") (pinfunction "6_6") (pintype "passive"))
    )
    (net (code "79") (name "unconnected-(GPS-Pad7)") (class "Default")
      (node (ref "GPS") (pin "7") (pinfunction "7_7") (pintype "passive"))
    )
    (net (code "80") (name "unconnected-(GPS-Pad8)") (class "Default")
      (node (ref "GPS") (pin "8") (pinfunction "8_8") (pintype "passive"))
    )
    (net (code "81") (name "unconnected-(GPS-Pad9)") (class "Default")
      (node (ref "GPS") (pin "9") (pinfunction "9_9") (pintype "passive"))
    )
    (net (code "82") (name "unconnected-(GPS-Pad10)") (class "Default")
      (node (ref "GPS") (pin "10") (pinfunction "10_10") (pintype "passive"))
    )
    (net (code "83") (name "unconnected-(J1-ID_SC-Pad28)") (class "Default")
      (node (ref "J1") (pin "28") (pinfunction "ID_SC_28") (pintype "bidirectional"))
    )
    (net (code "84") (name "unconnected-(J1-ID_SD-Pad27)") (class "Default")
      (node (ref "J1") (pin "27") (pinfunction "ID_SD_27") (pintype "bidirectional"))
    )
    (net (code "85") (name "unconnected-(THERMAL-Pad9)") (class "Default")
      (node (ref "THERMAL") (pin "9") (pinfunction "9_9") (pintype "passive"))
    )
    (net (code "86") (name "unconnected-(THERMAL-Pad10)") (class "Default")
      (node (ref "THERMAL") (pin "10") (pinfunction "10_10") (pintype "passive"))
    )
    (net (code "87") (name "unconnected-(U$2-PadIRQ)") (class "Default")
      (node (ref "U$2") (pin "IRQ") (pinfunction "IRQ_IRQ") (pintype "bidirectional"))
    )
    (net (code "88") (name "unconnected-(U1-~{INTA}-Pad3)") (class "Default")
      (node (ref "U1") (pin "3") (pinfunction "~{INTA}_3") (pintype "bidirectional"))
    )
    (net (code "89") (name "unconnected-(U1-~{INTB}-Pad7)") (class "Default")
      (node (ref "U1") (pin "7") (pinfunction "~{INTB}_7") (pintype "bidirectional"))
    )
    (net (code "90") (name "unconnected-(UT-1-Pad1)") (class "Default")
      (node (ref "UT-1") (pin "1") (pinfunction "1_1") (pintype "passive"))
    )
    (net (code "91") (name "unconnected-(UT-1-Pad3)") (class "Default")
      (node (ref "UT-1") (pin "3") (pinfunction "3_3") (pintype "passive"))
    )
    (net (code "92") (name "unconnected-(UT-1-Pad5)") (class "Default")
      (node (ref "UT-1") (pin "5") (pinfunction "5_5") (pintype "passive"))
    )
    (net (code "93") (name "unconnected-(UT-1-Pad8)") (class "Default")
      (node (ref "UT-1") (pin "8") (pinfunction "8_8") (pintype "passive"))
    )
    (net (code "94") (name "unconnected-(UT-1-Pad9)") (class "Default")
      (node (ref "UT-1") (pin "9") (pinfunction "9_9") (pintype "passive"))
    )
    (net (code "95") (name "unconnected-(UT-1-Pad10)") (class "Default")
      (node (ref "UT-1") (pin "10") (pinfunction "10_10") (pintype "passive"))
    )
    (net (code "96") (name "unconnected-(UT-2-Pad1)") (class "Default")
      (node (ref "UT-2") (pin "1") (pinfunction "1_1") (pintype "passive"))
    )
    (net (code "97") (name "unconnected-(UT-2-Pad3)") (class "Default")
      (node (ref "UT-2") (pin "3") (pinfunction "3_3") (pintype "passive"))
    )
    (net (code "98") (name "unconnected-(UT-2-Pad5)") (class "Default")
      (node (ref "UT-2") (pin "5") (pinfunction "5_5") (pintype "passive"))
    )
    (net (code "99") (name "unconnected-(UT-2-Pad8)") (class "Default")
      (node (ref "UT-2") (pin "8") (pinfunction "8_8") (pintype "passive"))
    )
    (net (code "100") (name "unconnected-(UT-2-Pad9)") (class "Default")
      (node (ref "UT-2") (pin "9") (pinfunction "9_9") (pintype "passive"))
    )
    (net (code "101") (name "unconnected-(UT-2-Pad10)") (class "Default")
      (node (ref "UT-2") (pin "10") (pinfunction "10_10") (pintype "passive"))
    )
    (net (code "102") (name "unconnected-(UT-3-Pad1)") (class "Default")
      (node (ref "UT-3") (pin "1") (pinfunction "1_1") (pintype "passive"))
    )
    (net (code "103") (name "unconnected-(UT-3-Pad3)") (class "Default")
      (node (ref "UT-3") (pin "3") (pinfunction "3_3") (pintype "passive"))
    )
    (net (code "104") (name "unconnected-(UT-3-Pad5)") (class "Default")
      (node (ref "UT-3") (pin "5") (pinfunction "5_5") (pintype "passive"))
    )
    (net (code "105") (name "unconnected-(UT-3-Pad8)") (class "Default")
      (node (ref "UT-3") (pin "8") (pinfunction "8_8") (pintype "passive"))
    )
    (net (code "106") (name "unconnected-(UT-3-Pad9)") (class "Default")
      (node (ref "UT-3") (pin "9") (pinfunction "9_9") (pintype "passive"))
    )
    (net (code "107") (name "unconnected-(UT-3-Pad10)") (class "Default")
      (node (ref "UT-3") (pin "10") (pinfunction "10_10") (pintype "passive"))
    )
    (net (code "108") (name "unconnected-(UT-4-Pad1)") (class "Default")
      (node (ref "UT-4") (pin "1") (pinfunction "1_1") (pintype "passive"))
    )
    (net (code "109") (name "unconnected-(UT-4-Pad3)") (class "Default")
      (node (ref "UT-4") (pin "3") (pinfunction "3_3") (pintype "passive"))
    )
    (net (code "110") (name "unconnected-(UT-4-Pad5)") (class "Default")
      (node (ref "UT-4") (pin "5") (pinfunction "5_5") (pintype "passive"))
    )
    (net (code "111") (name "unconnected-(UT-4-Pad8)") (class "Default")
      (node (ref "UT-4") (pin "8") (pinfunction "8_8") (pintype "passive"))
    )
    (net (code "112") (name "unconnected-(UT-4-Pad9)") (class "Default")
      (node (ref "UT-4") (pin "9") (pinfunction "9_9") (pintype "passive"))
    )
    (net (code "113") (name "unconnected-(UT-4-Pad10)") (class "Default")
      (node (ref "UT-4") (pin "10") (pinfunction "10_10") (pintype "passive"))
    )
    (net (code "114") (name "unconnected-(UT-5-Pad1)") (class "Default")
      (node (ref "UT-5") (pin "1") (pinfunction "1_1") (pintype "passive"))
    )
    (net (code "115") (name "unconnected-(UT-5-Pad3)") (class "Default")
      (node (ref "UT-5") (pin "3") (pinfunction "3_3") (pintype "passive"))
    )
    (net (code "116") (name "unconnected-(UT-5-Pad5)") (class "Default")
      (node (ref "UT-5") (pin "5") (pinfunction "5_5") (pintype "passive"))
    )
    (net (code "117") (name "unconnected-(UT-5-Pad8)") (class "Default")
      (node (ref "UT-5") (pin "8") (pinfunction "8_8") (pintype "passive"))
    )
    (net (code "118") (name "unconnected-(UT-5-Pad9)") (class "Default")
      (node (ref "UT-5") (pin "9") (pinfunction "9_9") (pintype "passive"))
    )
    (net (code "119") (name "unconnected-(UT-5-Pad10)") (class "Default")
      (node (ref "UT-5") (pin "10") (pinfunction "10_10") (pintype "passive"))
    )
    (net (code "120") (name "unconnected-(UT-6-Pad1)") (class "Default")
      (node (ref "UT-6") (pin "1") (pinfunction "1_1") (pintype "passive"))
    )
    (net (code "121") (name "unconnected-(UT-6-Pad3)") (class "Default")
      (node (ref "UT-6") (pin "3") (pinfunction "3_3") (pintype "passive"))
    )
    (net (code "122") (name "unconnected-(UT-6-Pad5)") (class "Default")
      (node (ref "UT-6") (pin "5") (pinfunction "5_5") (pintype "passive"))
    )
    (net (code "123") (name "unconnected-(UT-6-Pad8)") (class "Default")
      (node (ref "UT-6") (pin "8") (pinfunction "8_8") (pintype "passive"))
    )
    (net (code "124") (name "unconnected-(UT-6-Pad9)") (class "Default")
      (node (ref "UT-6") (pin "9") (pinfunction "9_9") (pintype "passive"))
    )
    (net (code "125") (name "unconnected-(UT-6-Pad10)") (class "Default")
      (node (ref "UT-6") (pin "10") (pinfunction "10_10") (pintype "passive"))
    )
  )
)
